# PS2Transiever.net
KiCad netlist of a schematic drawn in Altium Designer
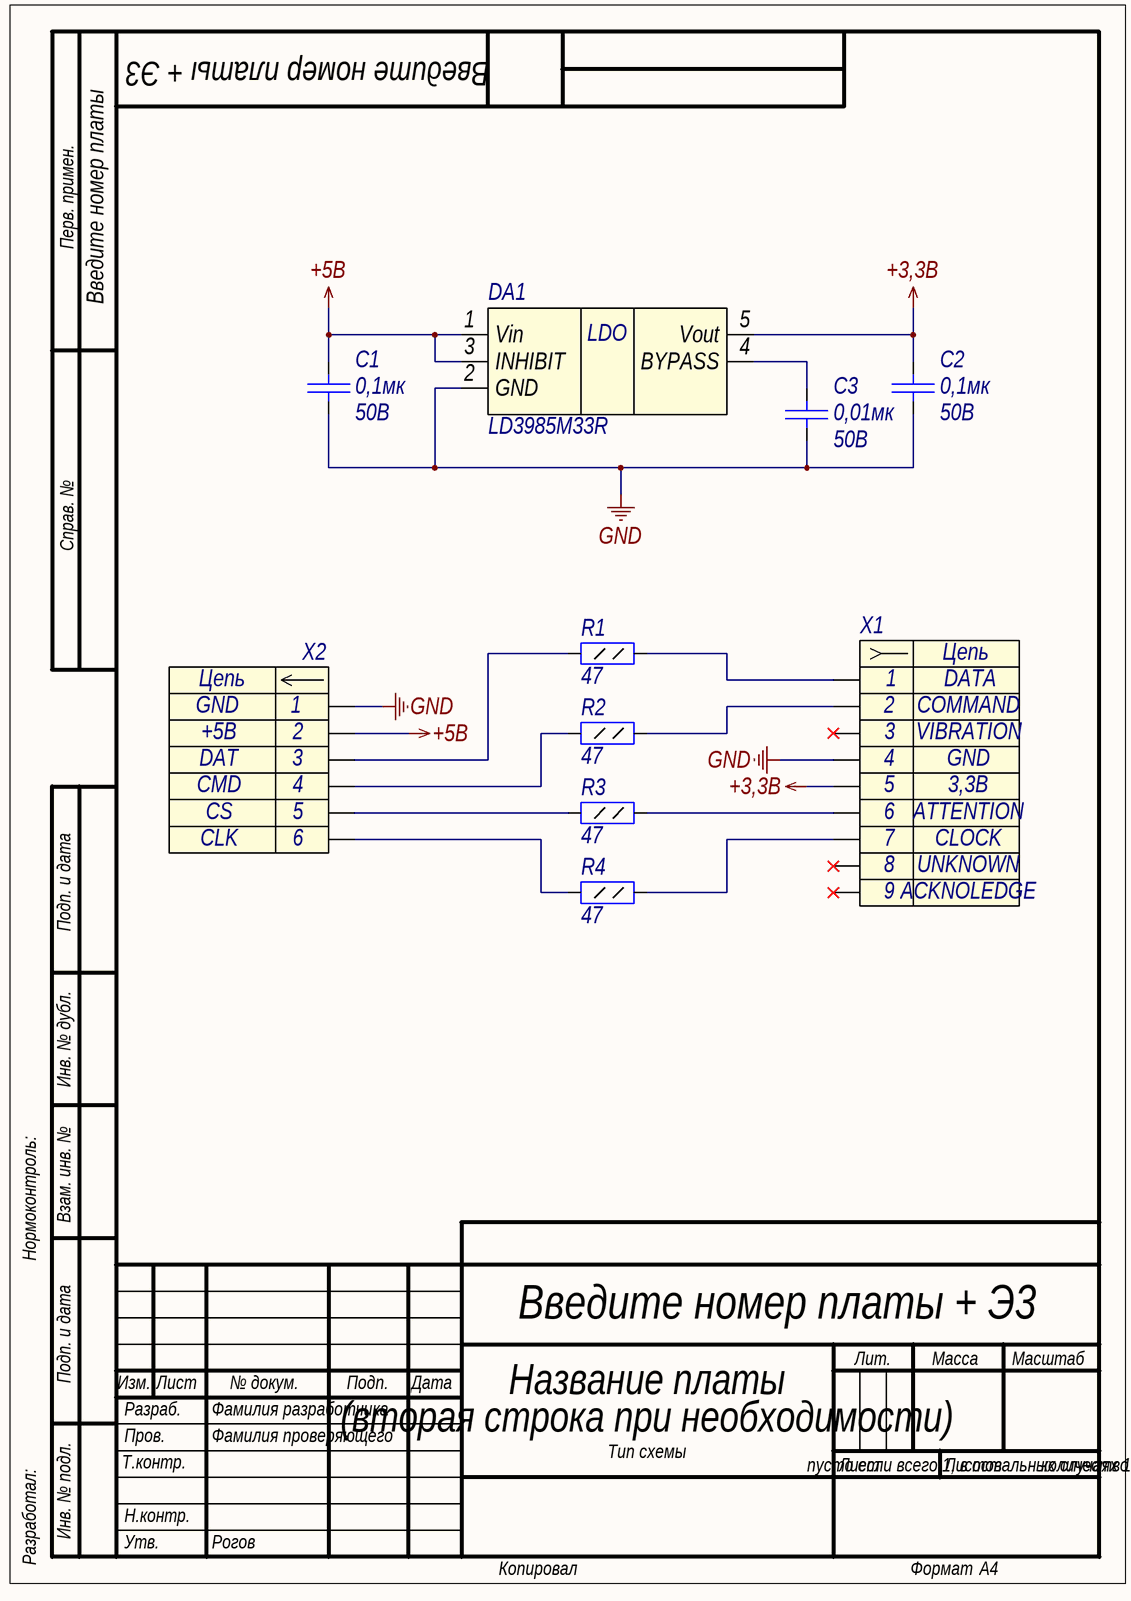
[diagram p0: PS2Transiever.SchDoc]

(export (version "E")
  (design (tool "Eeschema 10.0.6"))
  (components
    (comp (ref "C1")
      (value "0,1мк")
      (footprint "C0805")
      (description "Конденсатор")
      (fields (field (name "VOLTAGE") "50В") (field (name "PART NUMBER") "GRM21BR71H104KA01L "))
      (libsource (lib "MOP44") (part "Capacitor"))
    )
    (comp (ref "C2")
      (value "0,1мк")
      (footprint "C0805")
      (description "Конденсатор")
      (fields (field (name "VOLTAGE") "50В") (field (name "PART NUMBER") "GRM21BR71H104KA01L "))
      (libsource (lib "MOP44") (part "Capacitor"))
    )
    (comp (ref "C3")
      (value "0,01мк")
      (footprint "C0805")
      (description "Конденсатор")
      (fields (field (name "VOLTAGE") "50B") (field (name "PART NUMBER") "GRM216R71H103K"))
      (libsource (lib "MOP44") (part "Capacitor"))
    )
    (comp (ref "DA1")
      (value "LD3985")
      (footprint "SOT23-5")
      (description "Ultra low drop and low noise BiCMOS voltage regulators")
      (fields (field (name "PART NUMBER") "LD3985M33R") (field (name "MANUFACTURER") "ST Microelectronics"))
      (libsource (lib "MOP44") (part "LD3985"))
    )
    (comp (ref "R1")
      (value "47")
      (footprint "R0805")
      (description "Резистор")
      (fields (field (name "PART NUMBER") "RC0805FR-0747RL") (field (name "POWER") "0,125Вт"))
      (libsource (lib "MOP44") (part "Resistor_0,125Вт"))
    )
    (comp (ref "R2")
      (value "47")
      (footprint "R0805")
      (description "Резистор")
      (fields (field (name "PART NUMBER") "RC0805FR-0747RL") (field (name "POWER") "0,125Вт"))
      (libsource (lib "MOP44") (part "Resistor_0,125Вт"))
    )
    (comp (ref "R3")
      (value "47")
      (footprint "R0805")
      (description "Резистор")
      (fields (field (name "PART NUMBER") "RC0805FR-0747RL") (field (name "POWER") "0,125Вт"))
      (libsource (lib "MOP44") (part "Resistor_0,125Вт"))
    )
    (comp (ref "R4")
      (value "47")
      (footprint "R0805")
      (description "Резистор")
      (fields (field (name "PART NUMBER") "RC0805FR-0747RL") (field (name "POWER") "0,125Вт"))
      (libsource (lib "MOP44") (part "Resistor_0,125Вт"))
    )
    (comp (ref "X1")
      (value "Header_9_sct")
      (footprint "PS2-9PIN HEADER")
      (description "Разъем - 9 конт. розетка")
      (libsource (lib "MOP44") (part "Header_9_sct"))
    )
    (comp (ref "X2")
      (value "Header_6_plg")
      (footprint "PLS-6")
      (description "Разъем - 6 конт. вилка")
      (fields (field (name "PART NUMBER") "DS1021-1*6SF112-B"))
      (libsource (lib "MOP44") (part "Header_6_plg"))
    )
  )
  (nets
    (net (code "1") (name "+3,3B") (class "Default")
      (node (ref "C2") (pin "2") (pinfunction "2_2") (pintype "passive"))
      (node (ref "DA1") (pin "5") (pinfunction "Vout_5") (pintype "power_in"))
      (node (ref "X1") (pin "5") (pinfunction "5_5") (pintype "passive"))
    )
    (net (code "2") (name "+5B") (class "Default")
      (node (ref "C1") (pin "2") (pinfunction "2_2") (pintype "passive"))
      (node (ref "DA1") (pin "1") (pinfunction "Vin_1") (pintype "power_in"))
      (node (ref "DA1") (pin "3") (pinfunction "INHIBIT_3") (pintype "power_in"))
      (node (ref "X2") (pin "2") (pinfunction "2_2") (pintype "passive"))
    )
    (net (code "3") (name "GND") (class "Default")
      (node (ref "C1") (pin "1") (pinfunction "1_1") (pintype "passive"))
      (node (ref "C2") (pin "1") (pinfunction "1_1") (pintype "passive"))
      (node (ref "C3") (pin "1") (pinfunction "1_1") (pintype "passive"))
      (node (ref "DA1") (pin "2") (pinfunction "GND_2") (pintype "power_in"))
      (node (ref "X1") (pin "4") (pinfunction "4_4") (pintype "passive"))
      (node (ref "X2") (pin "1") (pinfunction "1_1") (pintype "passive"))
    )
    (net (code "4") (name "Net-(DA1-BYPASS)") (class "Default")
      (node (ref "C3") (pin "2") (pinfunction "2_2") (pintype "passive"))
      (node (ref "DA1") (pin "4") (pinfunction "BYPASS_4") (pintype "power_in"))
    )
    (net (code "5") (name "Net-(R1-Pad1)") (class "Default")
      (node (ref "R1") (pin "1") (pinfunction "1_1") (pintype "passive"))
      (node (ref "X1") (pin "1") (pinfunction "1_1") (pintype "passive"))
    )
    (net (code "6") (name "Net-(R1-Pad2)") (class "Default")
      (node (ref "R1") (pin "2") (pinfunction "2_2") (pintype "passive"))
      (node (ref "X2") (pin "3") (pinfunction "3_3") (pintype "passive"))
    )
    (net (code "7") (name "Net-(R2-Pad1)") (class "Default")
      (node (ref "R2") (pin "1") (pinfunction "1_1") (pintype "passive"))
      (node (ref "X1") (pin "2") (pinfunction "2_2") (pintype "passive"))
    )
    (net (code "8") (name "Net-(R2-Pad2)") (class "Default")
      (node (ref "R2") (pin "2") (pinfunction "2_2") (pintype "passive"))
      (node (ref "X2") (pin "4") (pinfunction "4_4") (pintype "passive"))
    )
    (net (code "9") (name "Net-(R3-Pad1)") (class "Default")
      (node (ref "R3") (pin "1") (pinfunction "1_1") (pintype "passive"))
      (node (ref "X1") (pin "6") (pinfunction "6_6") (pintype "passive"))
    )
    (net (code "10") (name "Net-(R3-Pad2)") (class "Default")
      (node (ref "R3") (pin "2") (pinfunction "2_2") (pintype "passive"))
      (node (ref "X2") (pin "5") (pinfunction "5_5") (pintype "passive"))
    )
    (net (code "11") (name "Net-(R4-Pad1)") (class "Default")
      (node (ref "R4") (pin "1") (pinfunction "1_1") (pintype "passive"))
      (node (ref "X1") (pin "7") (pinfunction "7_7") (pintype "passive"))
    )
    (net (code "12") (name "Net-(R4-Pad2)") (class "Default")
      (node (ref "R4") (pin "2") (pinfunction "2_2") (pintype "passive"))
      (node (ref "X2") (pin "6") (pinfunction "6_6") (pintype "passive"))
    )
    (net (code "13") (name "unconnected-(X1-Pad3)") (class "Default")
      (node (ref "X1") (pin "3") (pinfunction "3_3") (pintype "passive+no_connect"))
    )
    (net (code "14") (name "unconnected-(X1-Pad8)") (class "Default")
      (node (ref "X1") (pin "8") (pinfunction "8_8") (pintype "passive+no_connect"))
    )
    (net (code "15") (name "unconnected-(X1-Pad9)") (class "Default")
      (node (ref "X1") (pin "9") (pinfunction "9_9") (pintype "passive+no_connect"))
    )
  )
)
